# SCH_Final_2025-04-04.net
KiCad netlist of a schematic drawn in EasyEDA
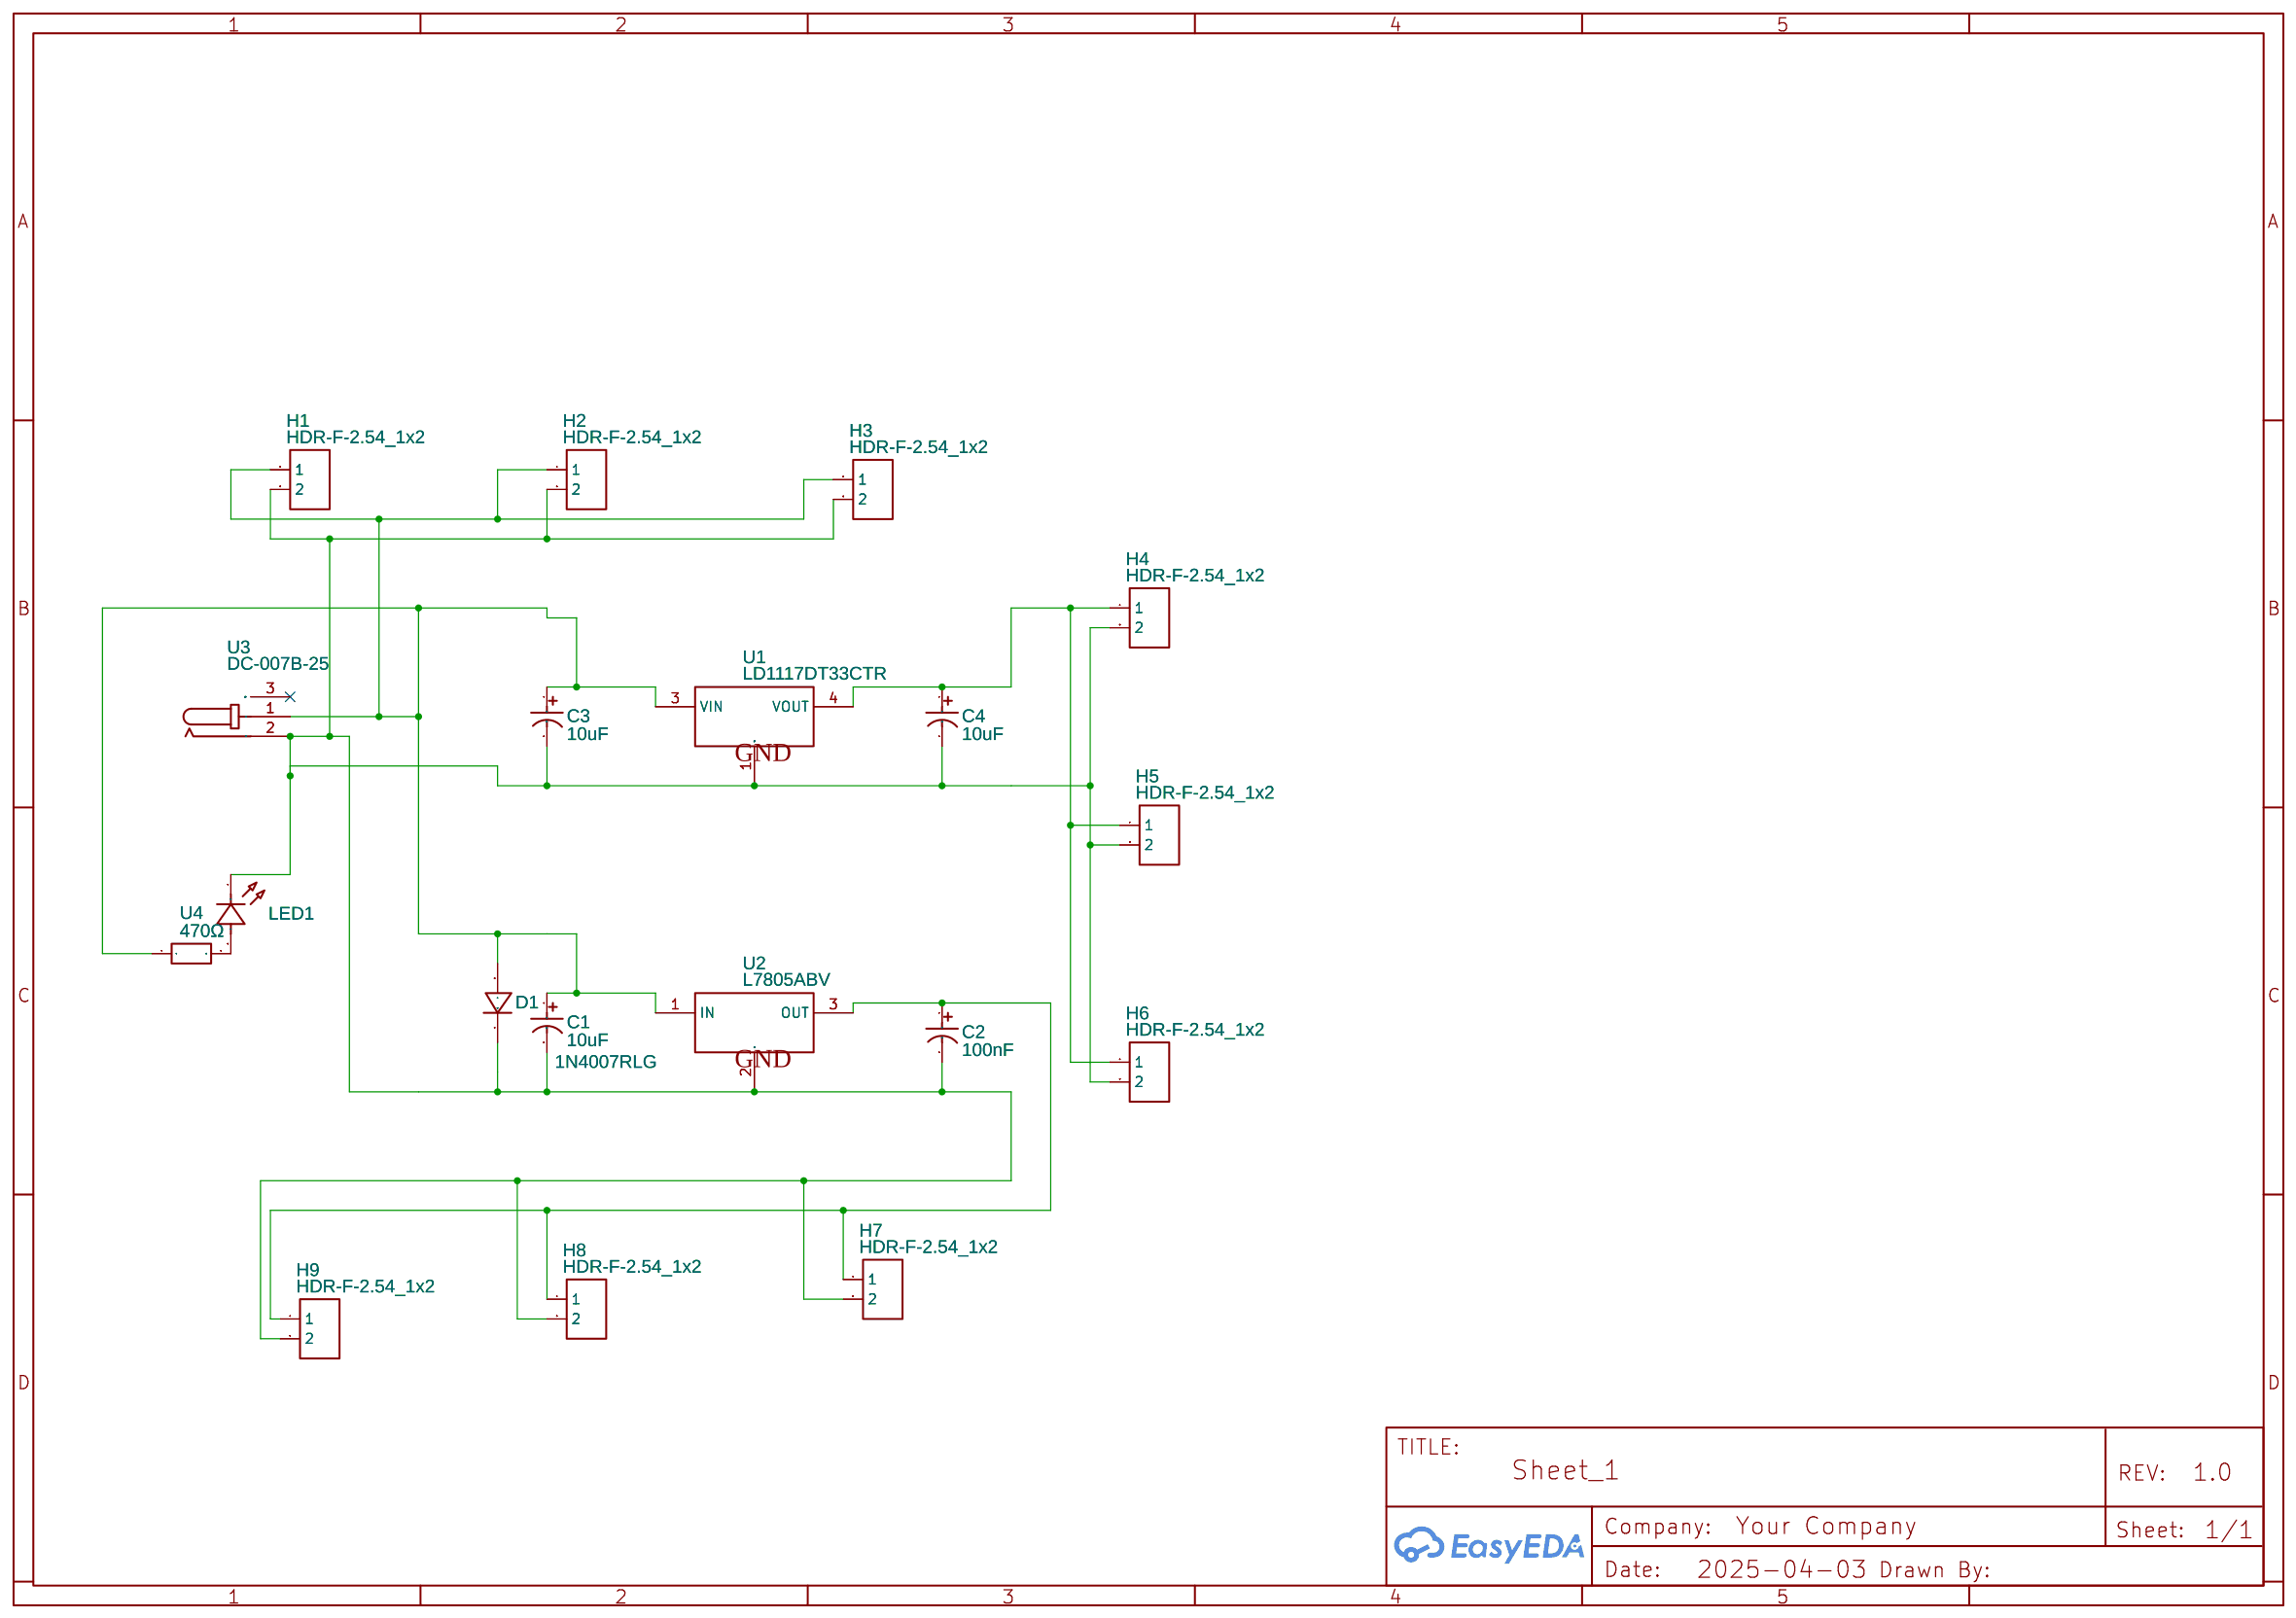
[diagram p0: schematic sheet]

(export (version "E")
  (design (tool "Eeschema 10.0.6"))
  (components
    (comp (ref "C1")
      (value "10uF")
      (fields
        (field (name "Manufacturer Part") "KF106M025C05RR0VH2FP0")
        (field (name "Manufacturer") "CX(承兴)")
      )
      (libsource (lib "") (part "10uF 25V 4*5"))
    )
    (comp (ref "C2")
      (value "100nF")
      (fields
        (field (name "Manufacturer Part") "KS104M050C07RR0VH2FP0")
        (field (name "Manufacturer") "CX(承兴)")
      )
      (libsource (lib "") (part "0.1uF 50V 4*7"))
    )
    (comp (ref "C3")
      (value "10uF")
      (fields
        (field (name "Manufacturer Part") "KF106M025C05RR0VH2FP0")
        (field (name "Manufacturer") "CX(承兴)")
      )
      (libsource (lib "") (part "10uF 25V 4*5"))
    )
    (comp (ref "C4")
      (value "10uF")
      (fields
        (field (name "Manufacturer Part") "KF106M025C05RR0VH2FP0")
        (field (name "Manufacturer") "CX(承兴)")
      )
      (libsource (lib "") (part "10uF 25V 4*5"))
    )
    (comp (ref "D1")
      (value "1N4007RLG")
      (fields (field (name "Manufacturer") "onsemi(安森美)"))
      (libsource (lib "") (part "1N4007RLG"))
    )
    (comp (ref "H1") (value "HDR-F-2.54_1x2") (libsource (lib "") (part "HDR-F-2.54_1x2")))
    (comp (ref "H2") (value "HDR-F-2.54_1x2") (libsource (lib "") (part "HDR-F-2.54_1x2")))
    (comp (ref "H3") (value "HDR-F-2.54_1x2") (libsource (lib "") (part "HDR-F-2.54_1x2")))
    (comp (ref "H4") (value "HDR-F-2.54_1x2") (libsource (lib "") (part "HDR-F-2.54_1x2")))
    (comp (ref "H5") (value "HDR-F-2.54_1x2") (libsource (lib "") (part "HDR-F-2.54_1x2")))
    (comp (ref "H6") (value "HDR-F-2.54_1x2") (libsource (lib "") (part "HDR-F-2.54_1x2")))
    (comp (ref "H7") (value "HDR-F-2.54_1x2") (libsource (lib "") (part "HDR-F-2.54_1x2")))
    (comp (ref "H8") (value "HDR-F-2.54_1x2") (libsource (lib "") (part "HDR-F-2.54_1x2")))
    (comp (ref "H9") (value "HDR-F-2.54_1x2") (libsource (lib "") (part "HDR-F-2.54_1x2")))
    (comp (ref "LED1")
      (value "F.0603.00013/P2-0603Y1TS2-06T-001")
      (fields (field (name "Manufacturer") "TUOZHAN(拓展光电)"))
      (libsource (lib "") (part "F.0603.00013/P2-0603Y1TS2-06T-001"))
    )
    (comp (ref "U1")
      (value "LD1117DT33CTR")
      (fields (field (name "Manufacturer") "ST(意法半导体)"))
      (libsource (lib "") (part "LD1117DT33CTR"))
    )
    (comp (ref "U2")
      (value "L7805ABV")
      (fields (field (name "Manufacturer") "ST(意法半导体)"))
      (libsource (lib "") (part "L7805ABV"))
    )
    (comp (ref "U3")
      (value "DC-007B-25")
      (fields (field (name "Manufacturer") "HanElectricity(瀚源)"))
      (libsource (lib "") (part "DC-007B-25"))
    )
    (comp (ref "U4")
      (value "470Ω")
      (fields (field (name "Manufacturer Part") "FRC0805J471 TS") (field (name "Manufacturer") "FOJAN(富捷)"))
      (libsource (lib "") (part "FRC0805J471 TS"))
    )
  )
  (nets
    (net (code "1") (name "Net-(D1-A)") (class "Default")
      (node (ref "C1") (pin "1") (pinfunction "1_1") (pintype "input"))
      (node (ref "C3") (pin "1") (pinfunction "1_1") (pintype "input"))
      (node (ref "D1") (pin "2") (pinfunction "A_2") (pintype "unspecified"))
      (node (ref "H1") (pin "1") (pinfunction "1_1") (pintype "input"))
      (node (ref "H2") (pin "1") (pinfunction "1_1") (pintype "input"))
      (node (ref "H3") (pin "1") (pinfunction "1_1") (pintype "input"))
      (node (ref "U1") (pin "3") (pinfunction "VIN_3") (pintype "passive"))
      (node (ref "U2") (pin "1") (pinfunction "IN_1") (pintype "passive"))
      (node (ref "U3") (pin "1") (pinfunction "1_1") (pintype "unspecified"))
      (node (ref "U4") (pin "1") (pinfunction "1_1") (pintype "unspecified"))
    )
    (net (code "2") (name "Net-(D1-C)") (class "Default")
      (node (ref "C1") (pin "2") (pinfunction "2_2") (pintype "input"))
      (node (ref "C2") (pin "2") (pinfunction "2_2") (pintype "input"))
      (node (ref "C3") (pin "2") (pinfunction "2_2") (pintype "input"))
      (node (ref "C4") (pin "2") (pinfunction "2_2") (pintype "input"))
      (node (ref "D1") (pin "1") (pinfunction "C_1") (pintype "unspecified"))
      (node (ref "H1") (pin "2") (pinfunction "2_2") (pintype "input"))
      (node (ref "H2") (pin "2") (pinfunction "2_2") (pintype "input"))
      (node (ref "H3") (pin "2") (pinfunction "2_2") (pintype "input"))
      (node (ref "H4") (pin "2") (pinfunction "2_2") (pintype "input"))
      (node (ref "H5") (pin "2") (pinfunction "2_2") (pintype "input"))
      (node (ref "H6") (pin "2") (pinfunction "2_2") (pintype "input"))
      (node (ref "H7") (pin "2") (pinfunction "2_2") (pintype "input"))
      (node (ref "H8") (pin "2") (pinfunction "2_2") (pintype "input"))
      (node (ref "H9") (pin "2") (pinfunction "2_2") (pintype "input"))
      (node (ref "LED1") (pin "1") (pinfunction "K_1") (pintype "unspecified"))
      (node (ref "U1") (pin "1") (pinfunction "GND_1") (pintype "passive"))
      (node (ref "U2") (pin "2") (pinfunction "GND_2") (pintype "passive"))
      (node (ref "U3") (pin "2") (pinfunction "2_2") (pintype "unspecified"))
    )
    (net (code "3") (name "Net-(LED1-A)") (class "Default")
      (node (ref "LED1") (pin "2") (pinfunction "A_2") (pintype "unspecified"))
      (node (ref "U4") (pin "2") (pinfunction "2_2") (pintype "unspecified"))
    )
    (net (code "4") (name "Net-(U1-VOUT)") (class "Default")
      (node (ref "C4") (pin "1") (pinfunction "1_1") (pintype "input"))
      (node (ref "H4") (pin "1") (pinfunction "1_1") (pintype "input"))
      (node (ref "H5") (pin "1") (pinfunction "1_1") (pintype "input"))
      (node (ref "H6") (pin "1") (pinfunction "1_1") (pintype "input"))
      (node (ref "U1") (pin "4") (pinfunction "VOUT_4") (pintype "passive"))
    )
    (net (code "5") (name "Net-(U2-OUT)") (class "Default")
      (node (ref "C2") (pin "1") (pinfunction "1_1") (pintype "input"))
      (node (ref "H7") (pin "1") (pinfunction "1_1") (pintype "input"))
      (node (ref "H8") (pin "1") (pinfunction "1_1") (pintype "input"))
      (node (ref "H9") (pin "1") (pinfunction "1_1") (pintype "input"))
      (node (ref "U2") (pin "3") (pinfunction "OUT_3") (pintype "passive"))
    )
    (net (code "6") (name "unconnected-(U3-SHELL-Pad3)") (class "Default")
      (node (ref "U3") (pin "3") (pinfunction "SHELL_3") (pintype "unspecified+no_connect"))
    )
  )
)
